# Microcontroller_Support.net
KiCad netlist of a schematic drawn in Altium Designer
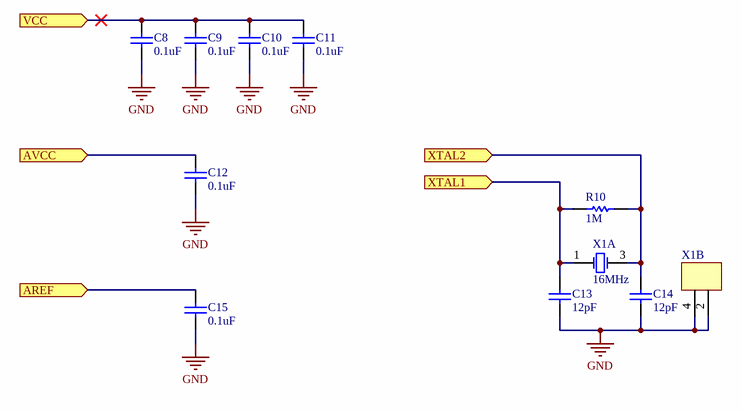
[diagram p0: Microcontroller Support.SchDoc]

(export (version "E")
  (design (tool "Eeschema 10.0.6"))
  (components
    (comp (ref "C8")
      (value "0.1uF")
      (footprint "CAPC0805(2012)100_M")
      (description "CAP 100nF 6.3V ±10% 0805 (2012 Metric) Thickness 1mm SMD")
      (fields (field (name "TOLERANCE") "Â±10%"))
      (libsource (lib "Altium Content Vault") (part "CAP"))
    )
    (comp (ref "C9")
      (value "0.1uF")
      (footprint "CAPC0805(2012)100_M")
      (description "CAP 100nF 6.3V ±10% 0805 (2012 Metric) Thickness 1mm SMD")
      (fields (field (name "TOLERANCE") "Â±10%"))
      (libsource (lib "Altium Content Vault") (part "CAP"))
    )
    (comp (ref "C10")
      (value "0.1uF")
      (footprint "CAPC0805(2012)100_M")
      (description "CAP 100nF 6.3V ±10% 0805 (2012 Metric) Thickness 1mm SMD")
      (fields (field (name "TOLERANCE") "Â±10%"))
      (libsource (lib "Altium Content Vault") (part "CAP"))
    )
    (comp (ref "C11")
      (value "0.1uF")
      (footprint "CAPC0805(2012)100_M")
      (description "CAP 100nF 6.3V ±10% 0805 (2012 Metric) Thickness 1mm SMD")
      (fields (field (name "TOLERANCE") "Â±10%"))
      (libsource (lib "Altium Content Vault") (part "CAP"))
    )
    (comp (ref "C12")
      (value "0.1uF")
      (footprint "CAPC0805(2012)100_M")
      (description "CAP 100nF 6.3V ±10% 0805 (2012 Metric) Thickness 1mm SMD")
      (fields (field (name "TOLERANCE") "Â±10%"))
      (libsource (lib "Altium Content Vault") (part "CAP"))
    )
    (comp (ref "C13")
      (value "12pF")
      (footprint "CAPC1608X87X35ML15T15")
      (fields (field (name "MANUFACTURER") "Kemet") (field (name "PART NUMBER") "C0603C120C5GACTU"))
      (libsource (lib "Altium Content Vault") (part "CAP"))
    )
    (comp (ref "C14")
      (value "12pF")
      (footprint "CAPC1608X87X35ML15T15")
      (fields (field (name "MANUFACTURER") "Kemet") (field (name "PART NUMBER") "C0603C120C5GACTU"))
      (libsource (lib "Altium Content Vault") (part "CAP"))
    )
    (comp (ref "C15")
      (value "0.1uF")
      (footprint "CAPC0805(2012)100_M")
      (description "CAP 100nF 6.3V ±10% 0805 (2012 Metric) Thickness 1mm SMD")
      (fields (field (name "TOLERANCE") "Â±10%"))
      (libsource (lib "Altium Content Vault") (part "CAP"))
    )
    (comp (ref "R10")
      (value "1M")
      (footprint "RESC2013X70X40NL20T20")
      (fields (field (name "MANUFACTURER") "Panasonic"))
      (libsource (lib "Altium Content Vault") (part "RES-2"))
    )
    (comp (ref "X1")
      (value "16MHz")
      (footprint "DFN220P320X80-4M")
      (description "CRYSTAL16MHZ 12PF SMD")
      (fields
        (field (name "MANUFACTURER") "Fox Electronics")
        (field (name "MANUFACTURER PART NUMBER") "FC3BACAGI16.0-T3")
      )
      (libsource (lib "Crystals") (part "FC3BACAGI16.0-T3"))
    )
  )
  (nets
    (net (code "1") (name "/AREF") (class "Default")
      (node (ref "C15") (pin "2") (pinfunction "2_2") (pintype "passive"))
    )
    (net (code "2") (name "/AVCC") (class "Default")
      (node (ref "C12") (pin "2") (pinfunction "2_2") (pintype "passive"))
    )
    (net (code "3") (name "/VCC") (class "Default")
      (node (ref "C10") (pin "2") (pinfunction "2_2") (pintype "passive"))
      (node (ref "C11") (pin "2") (pinfunction "2_2") (pintype "passive"))
      (node (ref "C8") (pin "2") (pinfunction "2_2") (pintype "passive"))
      (node (ref "C9") (pin "2") (pinfunction "2_2") (pintype "passive"))
    )
    (net (code "4") (name "/XTAL1") (class "Default")
      (node (ref "C13") (pin "2") (pinfunction "2_2") (pintype "passive"))
      (node (ref "R10") (pin "2") (pinfunction "2_2") (pintype "passive"))
      (node (ref "X1") (pin "1") (pinfunction "X1_1") (pintype "passive"))
    )
    (net (code "5") (name "/XTAL2") (class "Default")
      (node (ref "C14") (pin "2") (pinfunction "2_2") (pintype "passive"))
      (node (ref "R10") (pin "1") (pinfunction "1_1") (pintype "passive"))
      (node (ref "X1") (pin "3") (pinfunction "X2_3") (pintype "passive"))
    )
    (net (code "6") (name "GND") (class "Default")
      (node (ref "C10") (pin "1") (pinfunction "1_1") (pintype "passive"))
      (node (ref "C11") (pin "1") (pinfunction "1_1") (pintype "passive"))
      (node (ref "C12") (pin "1") (pinfunction "1_1") (pintype "passive"))
      (node (ref "C13") (pin "1") (pinfunction "1_1") (pintype "passive"))
      (node (ref "C14") (pin "1") (pinfunction "1_1") (pintype "passive"))
      (node (ref "C15") (pin "1") (pinfunction "1_1") (pintype "passive"))
      (node (ref "C8") (pin "1") (pinfunction "1_1") (pintype "passive"))
      (node (ref "C9") (pin "1") (pinfunction "1_1") (pintype "passive"))
      (node (ref "X1") (pin "2") (pinfunction "GND_2") (pintype "power_in"))
      (node (ref "X1") (pin "4") (pinfunction "GND_4") (pintype "power_in"))
    )
  )
)
